# Sheet1.net
KiCad netlist of a schematic drawn in Altium Designer
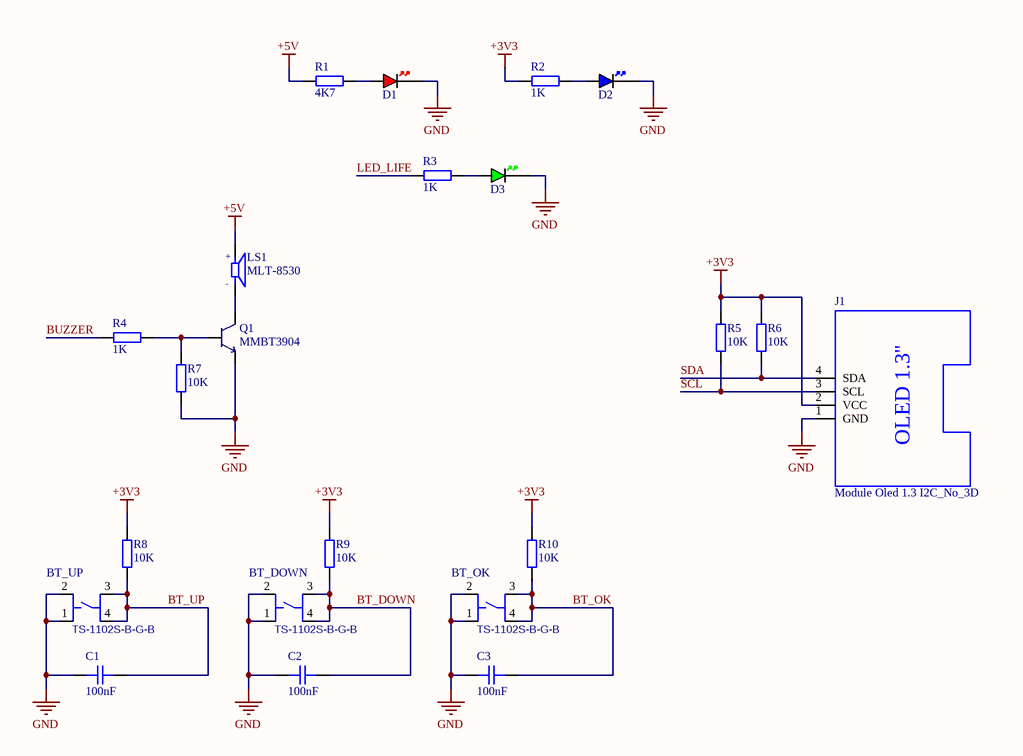
[diagram p0: Sheet1.SchDoc]

(export (version "E")
  (design (tool "Eeschema 10.0.6"))
  (components
    (comp (ref "BT_DOWN")
      (value "TS-1102S-B-G-B")
      (footprint "SW-SMD_4P-L6.0-W6.4-P4.50-LS8.6")
      (description "Botton SMD TACTILE SWITCHES ROHS")
      (fields (field (name "LCSC PART NUMBER") "C381064") (field (name "MANUFACTURER") "XKB Connectivity"))
      (libsource (lib "AK Base Kit 2.1") (part "TS-1102S-B-G-B"))
    )
    (comp (ref "BT_OK")
      (value "TS-1102S-B-G-B")
      (footprint "SW-SMD_4P-L6.0-W6.4-P4.50-LS8.6")
      (description "Botton SMD TACTILE SWITCHES ROHS")
      (fields (field (name "LCSC PART NUMBER") "C381064") (field (name "MANUFACTURER") "XKB Connectivity"))
      (libsource (lib "AK Base Kit 2.1") (part "TS-1102S-B-G-B"))
    )
    (comp (ref "BT_UP")
      (value "TS-1102S-B-G-B")
      (footprint "SW-SMD_4P-L6.0-W6.4-P4.50-LS8.6")
      (description "Botton SMD TACTILE SWITCHES ROHS")
      (fields (field (name "LCSC PART NUMBER") "C381064") (field (name "MANUFACTURER") "XKB Connectivity"))
      (libsource (lib "AK Base Kit 2.1") (part "TS-1102S-B-G-B"))
    )
    (comp (ref "C1")
      (value "100nF")
      (footprint "CAP_0603")
      (description "Capacitor SMD 0603")
      (libsource (lib "PhilsLab") (part "CAP_0603"))
    )
    (comp (ref "C2")
      (value "100nF")
      (footprint "CAP_0603")
      (description "Capacitor SMD 0603")
      (libsource (lib "PhilsLab") (part "CAP_0603"))
    )
    (comp (ref "C3")
      (value "100nF")
      (footprint "CAP_0603")
      (description "Capacitor SMD 0603")
      (libsource (lib "PhilsLab") (part "CAP_0603"))
    )
    (comp (ref "D1")
      (value "RED")
      (footprint "LED_0603_RED")
      (description "LED 0603 RED SMD")
      (libsource (lib "PhilsLab") (part "LED_0603_RED"))
    )
    (comp (ref "D2")
      (value "BLUE")
      (footprint "LED_0603_BLUE")
      (description "LED 0603 BLUE SMD")
      (libsource (lib "PhilsLab") (part "LED_0603_BLUE"))
    )
    (comp (ref "D3")
      (value "GREEN")
      (footprint "LED_0603_GREEN")
      (description "LED 0603 GREEN SMD")
      (libsource (lib "PhilsLab") (part "LED_0603_GREEN"))
    )
    (comp (ref "J1")
      (value "Module Oled 1.3 I2C_No_3D")
      (footprint "Module Oled 1.3 - No 3D")
      (description "Module Oled 1.3 I2C")
      (fields (field (name "MANUFACTURER") "EPCB.vn"))
      (libsource (lib "AK Base Kit 2.1") (part "Module Oled 1.3 I2C_No_3D"))
    )
    (comp (ref "LS1")
      (value "MLT-8530")
      (footprint "BUZ-SMD_4P-L8.5-W8.5-P8.50-BR")
      (description "BUZZERS MAGNETIC NO 2700HZ 3.6V 2.5 ~ 4.5V 8.5MM X 8.5MM 8.5*8.5*3MM ROHS")
      (fields (field (name "MANUFACTURER") "Jiangsu Huaneng Elec") (field (name "LCSC PART NUMBER") "C94599"))
      (libsource (lib "AK Base Kit 2.1") (part "BUZ_MLT-8530"))
    )
    (comp (ref "Q1")
      (value "MMBT3904")
      (footprint "SOT-23-3_L2.9-W1.3-P1.90-LS2.4-BR")
      (description "MMBT3904 TRANSISTORS (NPN/PNP) NPN 200MA 40V SOT-23(SOT-23-3) ROHS")
      (fields
        (field (name "MANUFACTURER") "Changjiang Electronics Tech (CJ)")
        (field (name "LCSC PART NUMBER") "C20526")
      )
      (libsource (lib "AK Base Kit 2.1") (part "MMBT3904"))
    )
    (comp (ref "R1")
      (value "4K7")
      (footprint "RES_0603")
      (description "Resistor SMD 0603")
      (libsource (lib "PhilsLab") (part "RES_0603"))
    )
    (comp (ref "R2")
      (value "1K")
      (footprint "RES_0603")
      (description "Resistor SMD 0603")
      (libsource (lib "PhilsLab") (part "RES_0603"))
    )
    (comp (ref "R3")
      (value "1K")
      (footprint "RES_0603")
      (description "Resistor SMD 0603")
      (libsource (lib "PhilsLab") (part "RES_0603"))
    )
    (comp (ref "R4")
      (value "1K")
      (footprint "RES_0603")
      (description "Resistor SMD 0603")
      (libsource (lib "PhilsLab") (part "RES_0603"))
    )
    (comp (ref "R5")
      (value "10K")
      (footprint "RES_0603")
      (description "Resistor SMD 0603")
      (libsource (lib "PhilsLab") (part "RES_0603"))
    )
    (comp (ref "R6")
      (value "10K")
      (footprint "RES_0603")
      (description "Resistor SMD 0603")
      (libsource (lib "PhilsLab") (part "RES_0603"))
    )
    (comp (ref "R7")
      (value "10K")
      (footprint "RES_0603")
      (description "Resistor SMD 0603")
      (libsource (lib "PhilsLab") (part "RES_0603"))
    )
    (comp (ref "R8")
      (value "10K")
      (footprint "RES_0603")
      (description "Resistor SMD 0603")
      (libsource (lib "PhilsLab") (part "RES_0603"))
    )
    (comp (ref "R9")
      (value "10K")
      (footprint "RES_0603")
      (description "Resistor SMD 0603")
      (libsource (lib "PhilsLab") (part "RES_0603"))
    )
    (comp (ref "R10")
      (value "10K")
      (footprint "RES_0603")
      (description "Resistor SMD 0603")
      (libsource (lib "PhilsLab") (part "RES_0603"))
    )
  )
  (nets
    (net (code "1") (name "+3V3") (class "Default")
      (node (ref "J1") (pin "2") (pinfunction "VCC_2") (pintype "passive"))
      (node (ref "R10") (pin "2") (pinfunction "2_2") (pintype "passive"))
      (node (ref "R2") (pin "1") (pinfunction "1_1") (pintype "passive"))
      (node (ref "R5") (pin "2") (pinfunction "2_2") (pintype "passive"))
      (node (ref "R6") (pin "2") (pinfunction "2_2") (pintype "passive"))
      (node (ref "R8") (pin "2") (pinfunction "2_2") (pintype "passive"))
      (node (ref "R9") (pin "2") (pinfunction "2_2") (pintype "passive"))
    )
    (net (code "2") (name "+5V") (class "Default")
      (node (ref "LS1") (pin "1") (pinfunction "1_1") (pintype "passive"))
      (node (ref "R1") (pin "1") (pinfunction "1_1") (pintype "passive"))
    )
    (net (code "3") (name "/BT_DOWN") (class "Default")
      (node (ref "BT_DOWN") (pin "3") (pinfunction "3_3") (pintype "passive"))
      (node (ref "BT_DOWN") (pin "4") (pinfunction "4_4") (pintype "passive"))
      (node (ref "C2") (pin "2") (pinfunction "2_2") (pintype "passive"))
      (node (ref "R9") (pin "1") (pinfunction "1_1") (pintype "passive"))
    )
    (net (code "4") (name "/BT_OK") (class "Default")
      (node (ref "BT_OK") (pin "3") (pinfunction "3_3") (pintype "passive"))
      (node (ref "BT_OK") (pin "4") (pinfunction "4_4") (pintype "passive"))
      (node (ref "C3") (pin "2") (pinfunction "2_2") (pintype "passive"))
      (node (ref "R10") (pin "1") (pinfunction "1_1") (pintype "passive"))
    )
    (net (code "5") (name "/BT_UP") (class "Default")
      (node (ref "BT_UP") (pin "3") (pinfunction "3_3") (pintype "passive"))
      (node (ref "BT_UP") (pin "4") (pinfunction "4_4") (pintype "passive"))
      (node (ref "C1") (pin "2") (pinfunction "2_2") (pintype "passive"))
      (node (ref "R8") (pin "1") (pinfunction "1_1") (pintype "passive"))
    )
    (net (code "6") (name "/BUZZER") (class "Default")
      (node (ref "R4") (pin "1") (pinfunction "1_1") (pintype "passive"))
    )
    (net (code "7") (name "/LED_LIFE") (class "Default")
      (node (ref "R3") (pin "1") (pinfunction "1_1") (pintype "passive"))
    )
    (net (code "8") (name "/SCL") (class "Default")
      (node (ref "J1") (pin "3") (pinfunction "SCL_3") (pintype "passive"))
      (node (ref "R5") (pin "1") (pinfunction "1_1") (pintype "passive"))
    )
    (net (code "9") (name "/SDA") (class "Default")
      (node (ref "J1") (pin "4") (pinfunction "SDA_4") (pintype "passive"))
      (node (ref "R6") (pin "1") (pinfunction "1_1") (pintype "passive"))
    )
    (net (code "10") (name "GND") (class "Default")
      (node (ref "BT_DOWN") (pin "1") (pinfunction "1_1") (pintype "passive"))
      (node (ref "BT_DOWN") (pin "2") (pinfunction "2_2") (pintype "passive"))
      (node (ref "BT_OK") (pin "1") (pinfunction "1_1") (pintype "passive"))
      (node (ref "BT_OK") (pin "2") (pinfunction "2_2") (pintype "passive"))
      (node (ref "BT_UP") (pin "1") (pinfunction "1_1") (pintype "passive"))
      (node (ref "BT_UP") (pin "2") (pinfunction "2_2") (pintype "passive"))
      (node (ref "C1") (pin "1") (pinfunction "1_1") (pintype "passive"))
      (node (ref "C2") (pin "1") (pinfunction "1_1") (pintype "passive"))
      (node (ref "C3") (pin "1") (pinfunction "1_1") (pintype "passive"))
      (node (ref "D1") (pin "K") (pinfunction "K_K") (pintype "passive"))
      (node (ref "D2") (pin "K") (pinfunction "K_K") (pintype "passive"))
      (node (ref "D3") (pin "K") (pinfunction "K_K") (pintype "passive"))
      (node (ref "J1") (pin "1") (pinfunction "GND_1") (pintype "passive"))
      (node (ref "Q1") (pin "2") (pinfunction "2_2") (pintype "power_in"))
      (node (ref "R7") (pin "1") (pinfunction "1_1") (pintype "passive"))
    )
    (net (code "11") (name "Net-(D1-PadA)") (class "Default")
      (node (ref "D1") (pin "A") (pinfunction "A_A") (pintype "passive"))
      (node (ref "R1") (pin "2") (pinfunction "2_2") (pintype "passive"))
    )
    (net (code "12") (name "Net-(D2-PadA)") (class "Default")
      (node (ref "D2") (pin "A") (pinfunction "A_A") (pintype "passive"))
      (node (ref "R2") (pin "2") (pinfunction "2_2") (pintype "passive"))
    )
    (net (code "13") (name "Net-(D3-PadA)") (class "Default")
      (node (ref "D3") (pin "A") (pinfunction "A_A") (pintype "passive"))
      (node (ref "R3") (pin "2") (pinfunction "2_2") (pintype "passive"))
    )
    (net (code "14") (name "Net-(LS1-Pad2)") (class "Default")
      (node (ref "LS1") (pin "2") (pinfunction "2_2") (pintype "passive"))
      (node (ref "Q1") (pin "3") (pinfunction "3_3") (pintype "power_in"))
    )
    (net (code "15") (name "Net-(Q1-Pad1)") (class "Default")
      (node (ref "Q1") (pin "1") (pinfunction "1_1") (pintype "power_in"))
      (node (ref "R4") (pin "2") (pinfunction "2_2") (pintype "passive"))
      (node (ref "R7") (pin "2") (pinfunction "2_2") (pintype "passive"))
    )
  )
)
